# LEDMatrix.net
KiCad netlist of a schematic drawn in EAGLE
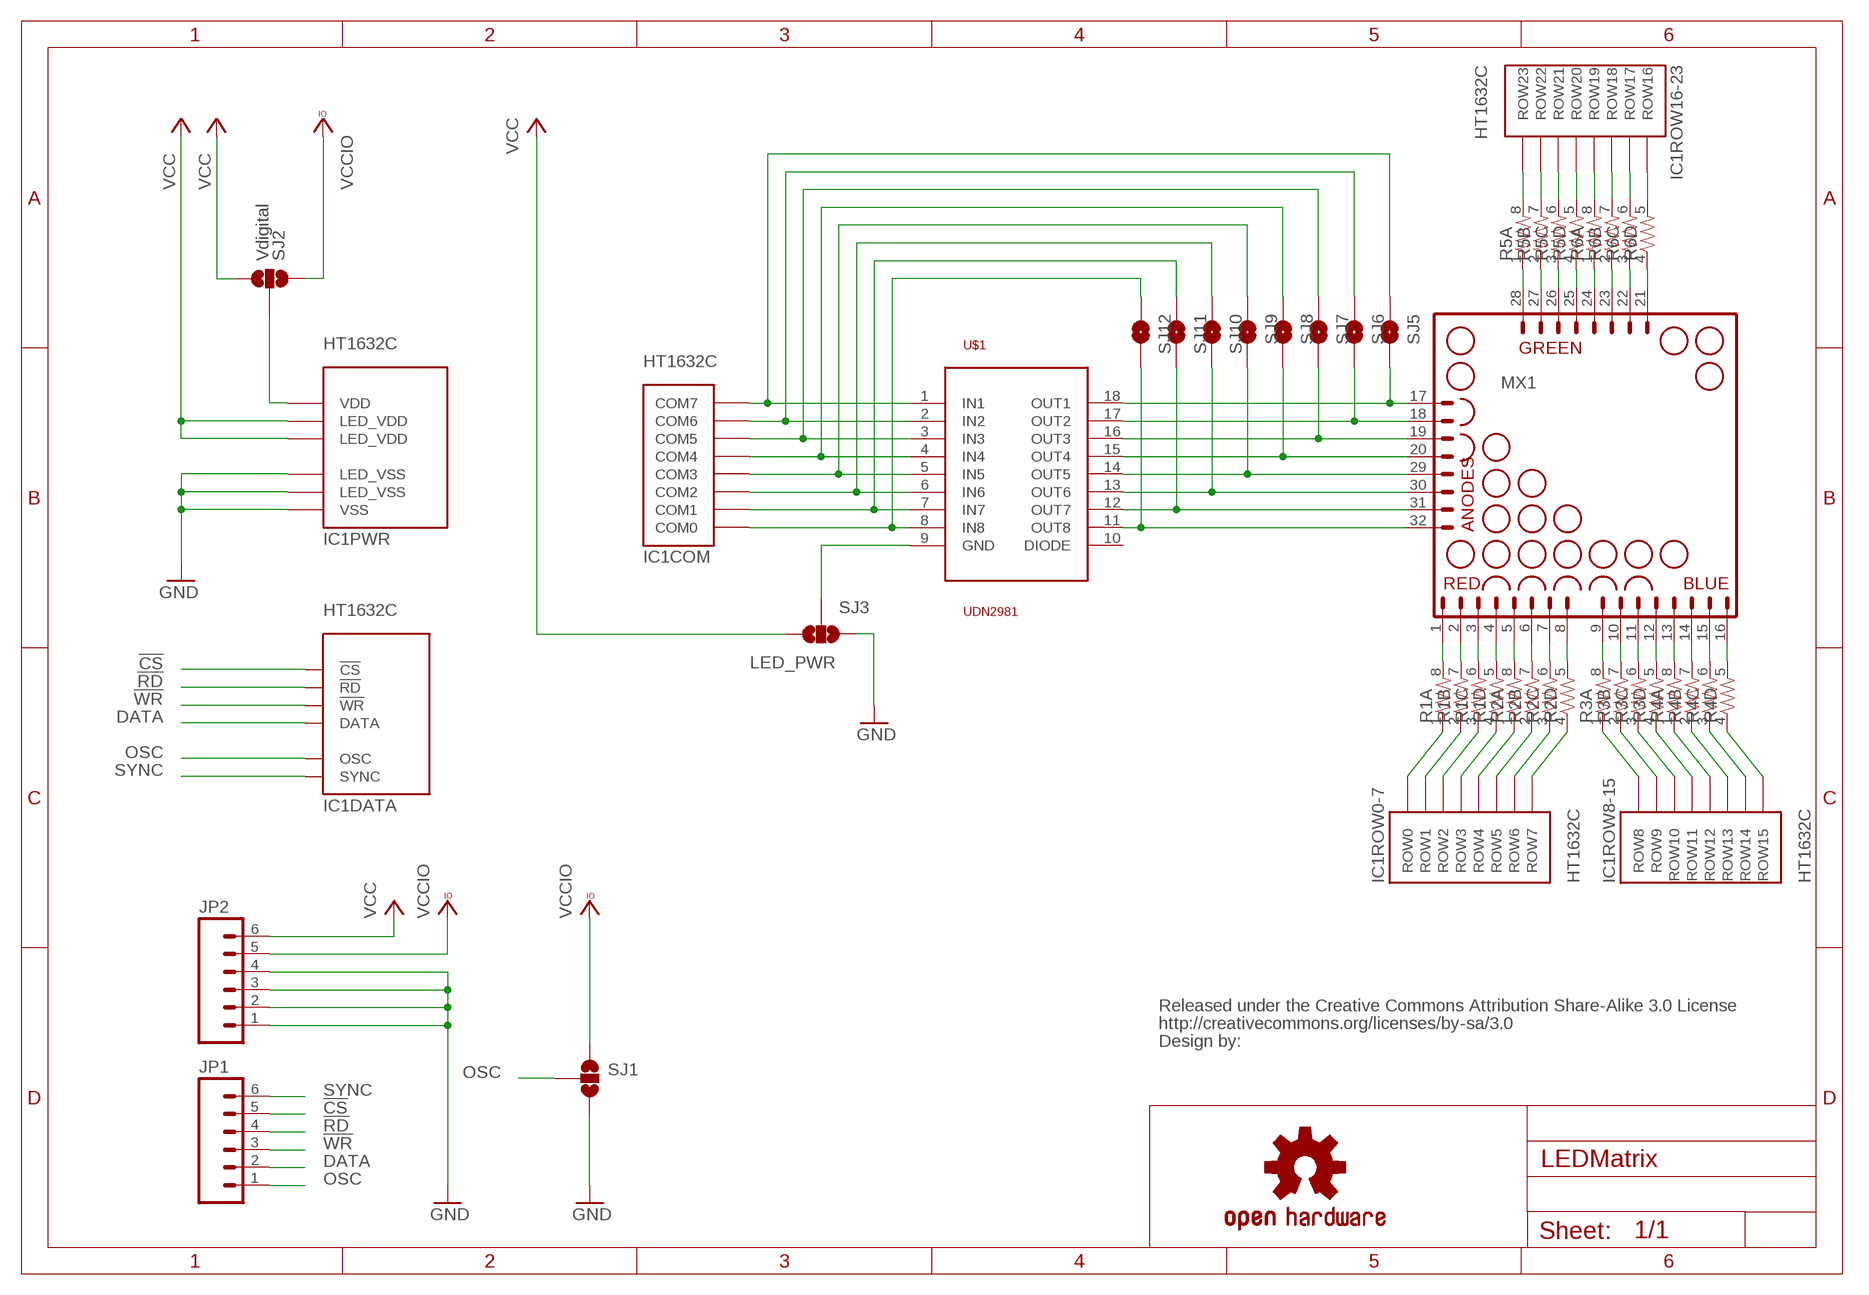
[diagram p0: schematic, sheet 1]

(export (version "E")
  (design (tool "Eeschema 10.0.6"))
  (components
    (comp (ref "CC_TEXT1")
      (value "CREATIVE_COMMONS")
      (footprint "eagle-import:CREATIVE_COMMONS")
      (libsource (lib "eagle-import") (part "CREATIVE_COMMONS"))
    )
    (comp (ref "IC1")
      (value "HT1632C")
      (footprint "eagle-import:QFP52")
      (libsource (lib "eagle-import") (part "HT1632"))
    )
    (comp (ref "JP1")
      (value "M06SIP")
      (footprint "eagle-import:1X06")
      (libsource (lib "eagle-import") (part "M06SIP"))
    )
    (comp (ref "JP2")
      (value "M06SIP")
      (footprint "eagle-import:1X06")
      (libsource (lib "eagle-import") (part "M06SIP"))
    )
    (comp (ref "LOGO1")
      (value "OSHW-LOGOL")
      (footprint "eagle-import:OSHW-LOGO-L")
      (libsource (lib "eagle-import") (part "OSHW-LOGOL"))
    )
    (comp (ref "MX1")
      (value "MATRIX_8X8_TRICOLOR_ANODE_ROW")
      (footprint "eagle-import:MATRIX_60MM_32PIN")
      (libsource (lib "eagle-import") (part "MATRIX_8X8_TRICOLOR_ANODE_ROW"))
    )
    (comp (ref "R1")
      (value "RESISTOR-ARRAY0603-ARV")
      (footprint "eagle-import:0603-ARV")
      (libsource (lib "eagle-import") (part "RESISTOR-ARRAY0603-ARV"))
    )
    (comp (ref "R2")
      (value "RESISTOR-ARRAY0603-ARV")
      (footprint "eagle-import:0603-ARV")
      (libsource (lib "eagle-import") (part "RESISTOR-ARRAY0603-ARV"))
    )
    (comp (ref "R3")
      (value "RESISTOR-ARRAY0603-ARV")
      (footprint "eagle-import:0603-ARV")
      (libsource (lib "eagle-import") (part "RESISTOR-ARRAY0603-ARV"))
    )
    (comp (ref "R4")
      (value "RESISTOR-ARRAY0603-ARV")
      (footprint "eagle-import:0603-ARV")
      (libsource (lib "eagle-import") (part "RESISTOR-ARRAY0603-ARV"))
    )
    (comp (ref "R5")
      (value "RESISTOR-ARRAY0603-ARV")
      (footprint "eagle-import:0603-ARV")
      (libsource (lib "eagle-import") (part "RESISTOR-ARRAY0603-ARV"))
    )
    (comp (ref "R6")
      (value "RESISTOR-ARRAY0603-ARV")
      (footprint "eagle-import:0603-ARV")
      (libsource (lib "eagle-import") (part "RESISTOR-ARRAY0603-ARV"))
    )
    (comp (ref "SJ1")
      (value "SOLDERJUMPER_2WAY-OLDS")
      (footprint "eagle-import:SJ_3")
      (libsource (lib "eagle-import") (part "SOLDERJUMPER_2WAY-OLDS"))
    )
    (comp (ref "SJ2")
      (value "Vdigital")
      (footprint "eagle-import:SJ_3")
      (libsource (lib "eagle-import") (part "SOLDERJUMPER_2WAY-OLDS"))
    )
    (comp (ref "SJ3")
      (value "LED_PWR")
      (footprint "eagle-import:SJ_3")
      (libsource (lib "eagle-import") (part "SOLDERJUMPER_2WAY-OLDS"))
    )
    (comp (ref "SJ5")
      (value "SOLDERJUMPER-OLDNO")
      (footprint "eagle-import:SJ_2S-NO")
      (libsource (lib "eagle-import") (part "SOLDERJUMPER-OLDNO"))
    )
    (comp (ref "SJ6")
      (value "SOLDERJUMPER-OLDNO")
      (footprint "eagle-import:SJ_2S-NO")
      (libsource (lib "eagle-import") (part "SOLDERJUMPER-OLDNO"))
    )
    (comp (ref "SJ7")
      (value "SOLDERJUMPER-OLDNO")
      (footprint "eagle-import:SJ_2S-NO")
      (libsource (lib "eagle-import") (part "SOLDERJUMPER-OLDNO"))
    )
    (comp (ref "SJ8")
      (value "SOLDERJUMPER-OLDNO")
      (footprint "eagle-import:SJ_2S-NO")
      (libsource (lib "eagle-import") (part "SOLDERJUMPER-OLDNO"))
    )
    (comp (ref "SJ9")
      (value "SOLDERJUMPER-OLDNO")
      (footprint "eagle-import:SJ_2S-NO")
      (libsource (lib "eagle-import") (part "SOLDERJUMPER-OLDNO"))
    )
    (comp (ref "SJ10")
      (value "SOLDERJUMPER-OLDNO")
      (footprint "eagle-import:SJ_2S-NO")
      (libsource (lib "eagle-import") (part "SOLDERJUMPER-OLDNO"))
    )
    (comp (ref "SJ11")
      (value "SOLDERJUMPER-OLDNO")
      (footprint "eagle-import:SJ_2S-NO")
      (libsource (lib "eagle-import") (part "SOLDERJUMPER-OLDNO"))
    )
    (comp (ref "SJ12")
      (value "SOLDERJUMPER-OLDNO")
      (footprint "eagle-import:SJ_2S-NO")
      (libsource (lib "eagle-import") (part "SOLDERJUMPER-OLDNO"))
    )
    (comp (ref "U$1")
      (value "UDN2981")
      (footprint "eagle-import:SO18L")
      (libsource (lib "eagle-import") (part "ULN2803"))
    )
  )
  (nets
    (net (code "1") (name "/DATA") (class "Default")
      (node (ref "IC1") (pin "P$16") (pinfunction "DATA_P$16") (pintype "bidirectional"))
      (node (ref "JP1") (pin "2") (pinfunction "2_2") (pintype "passive"))
    )
    (net (code "2") (name "/DIODE") (class "Default")
      (node (ref "U$1") (pin "10") (pinfunction "DIODE_10") (pintype "power_in"))
    )
    (net (code "3") (name "/OSC") (class "Default")
      (node (ref "IC1") (pin "P$15") (pinfunction "OSC_P$15") (pintype "bidirectional"))
      (node (ref "JP1") (pin "1") (pinfunction "1_1") (pintype "passive"))
      (node (ref "SJ1") (pin "2") (pinfunction "2_2") (pintype "passive"))
    )
    (net (code "4") (name "/SYNC") (class "Default")
      (node (ref "IC1") (pin "P$20") (pinfunction "SYNC_P$20") (pintype "bidirectional"))
      (node (ref "JP1") (pin "6") (pinfunction "6_6") (pintype "passive"))
    )
    (net (code "5") (name "/~{CS}") (class "Default")
      (node (ref "IC1") (pin "P$19") (pinfunction "~{CS}_P$19") (pintype "bidirectional"))
      (node (ref "JP1") (pin "5") (pinfunction "5_5") (pintype "passive"))
    )
    (net (code "6") (name "/~{RD}") (class "Default")
      (node (ref "IC1") (pin "P$18") (pinfunction "~{RD}_P$18") (pintype "bidirectional"))
      (node (ref "JP1") (pin "4") (pinfunction "4_4") (pintype "passive"))
    )
    (net (code "7") (name "/~{WR}") (class "Default")
      (node (ref "IC1") (pin "P$17") (pinfunction "~{WR}_P$17") (pintype "bidirectional"))
      (node (ref "JP1") (pin "3") (pinfunction "3_3") (pintype "passive"))
    )
    (net (code "8") (name "GND") (class "Default")
      (node (ref "IC1") (pin "P$14") (pinfunction "VSS_P$14") (pintype "bidirectional"))
      (node (ref "IC1") (pin "P$25") (pinfunction "LED_VSS_P$25") (pintype "bidirectional"))
      (node (ref "IC1") (pin "P$36") (pinfunction "LED_VSS_P$36") (pintype "bidirectional"))
      (node (ref "JP2") (pin "1") (pinfunction "1_1") (pintype "passive"))
      (node (ref "JP2") (pin "2") (pinfunction "2_2") (pintype "passive"))
      (node (ref "JP2") (pin "3") (pinfunction "3_3") (pintype "passive"))
      (node (ref "JP2") (pin "4") (pinfunction "4_4") (pintype "passive"))
      (node (ref "SJ1") (pin "3") (pinfunction "3_3") (pintype "passive"))
      (node (ref "SJ3") (pin "1") (pinfunction "1_1") (pintype "passive"))
    )
    (net (code "9") (name "Net-(IC1A-COM0)") (class "Default")
      (node (ref "IC1") (pin "P$22") (pinfunction "COM0_P$22") (pintype "bidirectional"))
      (node (ref "SJ12") (pin "1") (pinfunction "1_1") (pintype "passive"))
      (node (ref "U$1") (pin "8") (pinfunction "IN8_8") (pintype "input"))
    )
    (net (code "10") (name "Net-(IC1A-COM1)") (class "Default")
      (node (ref "IC1") (pin "P$23") (pinfunction "COM1_P$23") (pintype "bidirectional"))
      (node (ref "SJ11") (pin "1") (pinfunction "1_1") (pintype "passive"))
      (node (ref "U$1") (pin "7") (pinfunction "IN7_7") (pintype "input"))
    )
    (net (code "11") (name "Net-(IC1A-COM2)") (class "Default")
      (node (ref "IC1") (pin "P$24") (pinfunction "COM2_P$24") (pintype "bidirectional"))
      (node (ref "SJ10") (pin "1") (pinfunction "1_1") (pintype "passive"))
      (node (ref "U$1") (pin "6") (pinfunction "IN6_6") (pintype "input"))
    )
    (net (code "12") (name "Net-(IC1A-COM3)") (class "Default")
      (node (ref "IC1") (pin "P$26") (pinfunction "COM3_P$26") (pintype "bidirectional"))
      (node (ref "SJ9") (pin "1") (pinfunction "1_1") (pintype "passive"))
      (node (ref "U$1") (pin "5") (pinfunction "IN5_5") (pintype "input"))
    )
    (net (code "13") (name "Net-(IC1A-COM4)") (class "Default")
      (node (ref "IC1") (pin "P$27") (pinfunction "COM4_P$27") (pintype "bidirectional"))
      (node (ref "SJ8") (pin "1") (pinfunction "1_1") (pintype "passive"))
      (node (ref "U$1") (pin "4") (pinfunction "IN4_4") (pintype "input"))
    )
    (net (code "14") (name "Net-(IC1A-COM5)") (class "Default")
      (node (ref "IC1") (pin "P$28") (pinfunction "COM5_P$28") (pintype "bidirectional"))
      (node (ref "SJ7") (pin "1") (pinfunction "1_1") (pintype "passive"))
      (node (ref "U$1") (pin "3") (pinfunction "IN3_3") (pintype "input"))
    )
    (net (code "15") (name "Net-(IC1A-COM6)") (class "Default")
      (node (ref "IC1") (pin "P$29") (pinfunction "COM6_P$29") (pintype "bidirectional"))
      (node (ref "SJ6") (pin "1") (pinfunction "1_1") (pintype "passive"))
      (node (ref "U$1") (pin "2") (pinfunction "IN2_2") (pintype "input"))
    )
    (net (code "16") (name "Net-(IC1A-COM7)") (class "Default")
      (node (ref "IC1") (pin "P$30") (pinfunction "COM7_P$30") (pintype "bidirectional"))
      (node (ref "SJ5") (pin "1") (pinfunction "1_1") (pintype "passive"))
      (node (ref "U$1") (pin "1") (pinfunction "IN1_1") (pintype "input"))
    )
    (net (code "17") (name "Net-(IC1C-VDD)") (class "Default")
      (node (ref "IC1") (pin "P$21") (pinfunction "VDD_P$21") (pintype "bidirectional"))
      (node (ref "SJ2") (pin "2") (pinfunction "2_2") (pintype "passive"))
    )
    (net (code "18") (name "Net-(IC1D-ROW0)") (class "Default")
      (node (ref "IC1") (pin "P$13") (pinfunction "ROW0_P$13") (pintype "bidirectional"))
      (node (ref "R1") (pin "1") (pinfunction "1_1") (pintype "passive"))
    )
    (net (code "19") (name "Net-(IC1D-ROW1)") (class "Default")
      (node (ref "IC1") (pin "P$12") (pinfunction "ROW1_P$12") (pintype "bidirectional"))
      (node (ref "R1") (pin "2") (pinfunction "1_2") (pintype "passive"))
    )
    (net (code "20") (name "Net-(IC1D-ROW2)") (class "Default")
      (node (ref "IC1") (pin "P$11") (pinfunction "ROW2_P$11") (pintype "bidirectional"))
      (node (ref "R1") (pin "3") (pinfunction "1_3") (pintype "passive"))
    )
    (net (code "21") (name "Net-(IC1D-ROW3)") (class "Default")
      (node (ref "IC1") (pin "P$10") (pinfunction "ROW3_P$10") (pintype "bidirectional"))
      (node (ref "R1") (pin "4") (pinfunction "1_4") (pintype "passive"))
    )
    (net (code "22") (name "Net-(IC1D-ROW4)") (class "Default")
      (node (ref "IC1") (pin "P$9") (pinfunction "ROW4_P$9") (pintype "bidirectional"))
      (node (ref "R2") (pin "1") (pinfunction "1_1") (pintype "passive"))
    )
    (net (code "23") (name "Net-(IC1D-ROW5)") (class "Default")
      (node (ref "IC1") (pin "P$8") (pinfunction "ROW5_P$8") (pintype "bidirectional"))
      (node (ref "R2") (pin "2") (pinfunction "1_2") (pintype "passive"))
    )
    (net (code "24") (name "Net-(IC1D-ROW6)") (class "Default")
      (node (ref "IC1") (pin "P$6") (pinfunction "ROW6_P$6") (pintype "bidirectional"))
      (node (ref "R2") (pin "3") (pinfunction "1_3") (pintype "passive"))
    )
    (net (code "25") (name "Net-(IC1D-ROW7)") (class "Default")
      (node (ref "IC1") (pin "P$5") (pinfunction "ROW7_P$5") (pintype "bidirectional"))
      (node (ref "R2") (pin "4") (pinfunction "1_4") (pintype "passive"))
    )
    (net (code "26") (name "Net-(IC1E-ROW16)") (class "Default")
      (node (ref "IC1") (pin "P$48") (pinfunction "ROW16_P$48") (pintype "bidirectional"))
      (node (ref "R6") (pin "5") (pinfunction "2_5") (pintype "passive"))
    )
    (net (code "27") (name "Net-(IC1E-ROW17)") (class "Default")
      (node (ref "IC1") (pin "P$47") (pinfunction "ROW17_P$47") (pintype "bidirectional"))
      (node (ref "R6") (pin "6") (pinfunction "2_6") (pintype "passive"))
    )
    (net (code "28") (name "Net-(IC1E-ROW18)") (class "Default")
      (node (ref "IC1") (pin "P$46") (pinfunction "ROW18_P$46") (pintype "bidirectional"))
      (node (ref "R6") (pin "7") (pinfunction "2_7") (pintype "passive"))
    )
    (net (code "29") (name "Net-(IC1E-ROW19)") (class "Default")
      (node (ref "IC1") (pin "P$45") (pinfunction "ROW19_P$45") (pintype "bidirectional"))
      (node (ref "R6") (pin "8") (pinfunction "2_8") (pintype "passive"))
    )
    (net (code "30") (name "Net-(IC1E-ROW20)") (class "Default")
      (node (ref "IC1") (pin "P$44") (pinfunction "ROW20_P$44") (pintype "bidirectional"))
      (node (ref "R5") (pin "5") (pinfunction "2_5") (pintype "passive"))
    )
    (net (code "31") (name "Net-(IC1E-ROW21)") (class "Default")
      (node (ref "IC1") (pin "P$43") (pinfunction "ROW21_P$43") (pintype "bidirectional"))
      (node (ref "R5") (pin "6") (pinfunction "2_6") (pintype "passive"))
    )
    (net (code "32") (name "Net-(IC1E-ROW22)") (class "Default")
      (node (ref "IC1") (pin "P$42") (pinfunction "ROW22_P$42") (pintype "bidirectional"))
      (node (ref "R5") (pin "7") (pinfunction "2_7") (pintype "passive"))
    )
    (net (code "33") (name "Net-(IC1E-ROW23)") (class "Default")
      (node (ref "IC1") (pin "P$41") (pinfunction "ROW23_P$41") (pintype "bidirectional"))
      (node (ref "R5") (pin "8") (pinfunction "2_8") (pintype "passive"))
    )
    (net (code "34") (name "Net-(IC1G-ROW8)") (class "Default")
      (node (ref "IC1") (pin "P$4") (pinfunction "ROW8_P$4") (pintype "bidirectional"))
      (node (ref "R3") (pin "1") (pinfunction "1_1") (pintype "passive"))
    )
    (net (code "35") (name "Net-(IC1G-ROW9)") (class "Default")
      (node (ref "IC1") (pin "P$3") (pinfunction "ROW9_P$3") (pintype "bidirectional"))
      (node (ref "R3") (pin "2") (pinfunction "1_2") (pintype "passive"))
    )
    (net (code "36") (name "Net-(IC1G-ROW10)") (class "Default")
      (node (ref "IC1") (pin "P$2") (pinfunction "ROW10_P$2") (pintype "bidirectional"))
      (node (ref "R3") (pin "3") (pinfunction "1_3") (pintype "passive"))
    )
    (net (code "37") (name "Net-(IC1G-ROW11)") (class "Default")
      (node (ref "IC1") (pin "P$1") (pinfunction "ROW11_P$1") (pintype "bidirectional"))
      (node (ref "R3") (pin "4") (pinfunction "1_4") (pintype "passive"))
    )
    (net (code "38") (name "Net-(IC1G-ROW12)") (class "Default")
      (node (ref "IC1") (pin "P$52") (pinfunction "ROW12_P$52") (pintype "bidirectional"))
      (node (ref "R4") (pin "1") (pinfunction "1_1") (pintype "passive"))
    )
    (net (code "39") (name "Net-(IC1G-ROW13)") (class "Default")
      (node (ref "IC1") (pin "P$51") (pinfunction "ROW13_P$51") (pintype "bidirectional"))
      (node (ref "R4") (pin "2") (pinfunction "1_2") (pintype "passive"))
    )
    (net (code "40") (name "Net-(IC1G-ROW14)") (class "Default")
      (node (ref "IC1") (pin "P$50") (pinfunction "ROW14_P$50") (pintype "bidirectional"))
      (node (ref "R4") (pin "3") (pinfunction "1_3") (pintype "passive"))
    )
    (net (code "41") (name "Net-(IC1G-ROW15)") (class "Default")
      (node (ref "IC1") (pin "P$49") (pinfunction "ROW15_P$49") (pintype "bidirectional"))
      (node (ref "R4") (pin "4") (pinfunction "1_4") (pintype "passive"))
    )
    (net (code "42") (name "Net-(MX1-Pad24)") (class "Default")
      (node (ref "MX1") (pin "24") (pinfunction "24_24") (pintype "passive"))
      (node (ref "R6") (pin "1") (pinfunction "1_1") (pintype "passive"))
    )
    (net (code "43") (name "Net-(MX1-Pad28)") (class "Default")
      (node (ref "MX1") (pin "28") (pinfunction "28_28") (pintype "passive"))
      (node (ref "R5") (pin "1") (pinfunction "1_1") (pintype "passive"))
    )
    (net (code "44") (name "Net-(R1A-2)") (class "Default")
      (node (ref "MX1") (pin "1") (pinfunction "1_1") (pintype "passive"))
      (node (ref "R1") (pin "8") (pinfunction "2_8") (pintype "passive"))
    )
    (net (code "45") (name "Net-(R1B-2)") (class "Default")
      (node (ref "MX1") (pin "2") (pinfunction "2_2") (pintype "passive"))
      (node (ref "R1") (pin "7") (pinfunction "2_7") (pintype "passive"))
    )
    (net (code "46") (name "Net-(R1C-2)") (class "Default")
      (node (ref "MX1") (pin "3") (pinfunction "3_3") (pintype "passive"))
      (node (ref "R1") (pin "6") (pinfunction "2_6") (pintype "passive"))
    )
    (net (code "47") (name "Net-(R1D-2)") (class "Default")
      (node (ref "MX1") (pin "4") (pinfunction "4_4") (pintype "passive"))
      (node (ref "R1") (pin "5") (pinfunction "2_5") (pintype "passive"))
    )
    (net (code "48") (name "Net-(R2A-2)") (class "Default")
      (node (ref "MX1") (pin "5") (pinfunction "5_5") (pintype "passive"))
      (node (ref "R2") (pin "8") (pinfunction "2_8") (pintype "passive"))
    )
    (net (code "49") (name "Net-(R2B-2)") (class "Default")
      (node (ref "MX1") (pin "6") (pinfunction "6_6") (pintype "passive"))
      (node (ref "R2") (pin "7") (pinfunction "2_7") (pintype "passive"))
    )
    (net (code "50") (name "Net-(R2C-2)") (class "Default")
      (node (ref "MX1") (pin "7") (pinfunction "7_7") (pintype "passive"))
      (node (ref "R2") (pin "6") (pinfunction "2_6") (pintype "passive"))
    )
    (net (code "51") (name "Net-(R2D-2)") (class "Default")
      (node (ref "MX1") (pin "8") (pinfunction "8_8") (pintype "passive"))
      (node (ref "R2") (pin "5") (pinfunction "2_5") (pintype "passive"))
    )
    (net (code "52") (name "Net-(R3A-2)") (class "Default")
      (node (ref "MX1") (pin "9") (pinfunction "9_9") (pintype "passive"))
      (node (ref "R3") (pin "8") (pinfunction "2_8") (pintype "passive"))
    )
    (net (code "53") (name "Net-(R3B-2)") (class "Default")
      (node (ref "MX1") (pin "10") (pinfunction "10_10") (pintype "passive"))
      (node (ref "R3") (pin "7") (pinfunction "2_7") (pintype "passive"))
    )
    (net (code "54") (name "Net-(R3C-2)") (class "Default")
      (node (ref "MX1") (pin "11") (pinfunction "11_11") (pintype "passive"))
      (node (ref "R3") (pin "6") (pinfunction "2_6") (pintype "passive"))
    )
    (net (code "55") (name "Net-(R3D-2)") (class "Default")
      (node (ref "MX1") (pin "12") (pinfunction "12_12") (pintype "passive"))
      (node (ref "R3") (pin "5") (pinfunction "2_5") (pintype "passive"))
    )
    (net (code "56") (name "Net-(R4A-2)") (class "Default")
      (node (ref "MX1") (pin "13") (pinfunction "13_13") (pintype "passive"))
      (node (ref "R4") (pin "8") (pinfunction "2_8") (pintype "passive"))
    )
    (net (code "57") (name "Net-(R4B-2)") (class "Default")
      (node (ref "MX1") (pin "14") (pinfunction "14_14") (pintype "passive"))
      (node (ref "R4") (pin "7") (pinfunction "2_7") (pintype "passive"))
    )
    (net (code "58") (name "Net-(R4C-2)") (class "Default")
      (node (ref "MX1") (pin "15") (pinfunction "15_15") (pintype "passive"))
      (node (ref "R4") (pin "6") (pinfunction "2_6") (pintype "passive"))
    )
    (net (code "59") (name "Net-(R4D-2)") (class "Default")
      (node (ref "MX1") (pin "16") (pinfunction "16_16") (pintype "passive"))
      (node (ref "R4") (pin "5") (pinfunction "2_5") (pintype "passive"))
    )
    (net (code "60") (name "Net-(R5B-1)") (class "Default")
      (node (ref "MX1") (pin "27") (pinfunction "27_27") (pintype "passive"))
      (node (ref "R5") (pin "2") (pinfunction "1_2") (pintype "passive"))
    )
    (net (code "61") (name "Net-(R5C-1)") (class "Default")
      (node (ref "MX1") (pin "26") (pinfunction "26_26") (pintype "passive"))
      (node (ref "R5") (pin "3") (pinfunction "1_3") (pintype "passive"))
    )
    (net (code "62") (name "Net-(R5D-1)") (class "Default")
      (node (ref "MX1") (pin "25") (pinfunction "25_25") (pintype "passive"))
      (node (ref "R5") (pin "4") (pinfunction "1_4") (pintype "passive"))
    )
    (net (code "63") (name "Net-(R6B-1)") (class "Default")
      (node (ref "MX1") (pin "23") (pinfunction "23_23") (pintype "passive"))
      (node (ref "R6") (pin "2") (pinfunction "1_2") (pintype "passive"))
    )
    (net (code "64") (name "Net-(R6C-1)") (class "Default")
      (node (ref "MX1") (pin "22") (pinfunction "22_22") (pintype "passive"))
      (node (ref "R6") (pin "3") (pinfunction "1_3") (pintype "passive"))
    )
    (net (code "65") (name "Net-(R6D-1)") (class "Default")
      (node (ref "MX1") (pin "21") (pinfunction "21_21") (pintype "passive"))
      (node (ref "R6") (pin "4") (pinfunction "1_4") (pintype "passive"))
    )
    (net (code "66") (name "Net-(U$1-GND)") (class "Default")
      (node (ref "SJ3") (pin "2") (pinfunction "2_2") (pintype "passive"))
      (node (ref "U$1") (pin "9") (pinfunction "GND_9") (pintype "power_in"))
    )
    (net (code "67") (name "Net-(U$1-OUT1)") (class "Default")
      (node (ref "MX1") (pin "17") (pinfunction "17_17") (pintype "passive"))
      (node (ref "SJ5") (pin "2") (pinfunction "2_2") (pintype "passive"))
      (node (ref "U$1") (pin "18") (pinfunction "OUT1_18") (pintype "open_collector"))
    )
    (net (code "68") (name "Net-(U$1-OUT2)") (class "Default")
      (node (ref "MX1") (pin "18") (pinfunction "18_18") (pintype "passive"))
      (node (ref "SJ6") (pin "2") (pinfunction "2_2") (pintype "passive"))
      (node (ref "U$1") (pin "17") (pinfunction "OUT2_17") (pintype "open_collector"))
    )
    (net (code "69") (name "Net-(U$1-OUT3)") (class "Default")
      (node (ref "MX1") (pin "19") (pinfunction "19_19") (pintype "passive"))
      (node (ref "SJ7") (pin "2") (pinfunction "2_2") (pintype "passive"))
      (node (ref "U$1") (pin "16") (pinfunction "OUT3_16") (pintype "open_collector"))
    )
    (net (code "70") (name "Net-(U$1-OUT4)") (class "Default")
      (node (ref "MX1") (pin "20") (pinfunction "20_20") (pintype "passive"))
      (node (ref "SJ8") (pin "2") (pinfunction "2_2") (pintype "passive"))
      (node (ref "U$1") (pin "15") (pinfunction "OUT4_15") (pintype "open_collector"))
    )
    (net (code "71") (name "Net-(U$1-OUT5)") (class "Default")
      (node (ref "MX1") (pin "29") (pinfunction "29_29") (pintype "passive"))
      (node (ref "SJ9") (pin "2") (pinfunction "2_2") (pintype "passive"))
      (node (ref "U$1") (pin "14") (pinfunction "OUT5_14") (pintype "open_collector"))
    )
    (net (code "72") (name "Net-(U$1-OUT6)") (class "Default")
      (node (ref "MX1") (pin "30") (pinfunction "30_30") (pintype "passive"))
      (node (ref "SJ10") (pin "2") (pinfunction "2_2") (pintype "passive"))
      (node (ref "U$1") (pin "13") (pinfunction "OUT6_13") (pintype "open_collector"))
    )
    (net (code "73") (name "Net-(U$1-OUT7)") (class "Default")
      (node (ref "MX1") (pin "31") (pinfunction "31_31") (pintype "passive"))
      (node (ref "SJ11") (pin "2") (pinfunction "2_2") (pintype "passive"))
      (node (ref "U$1") (pin "12") (pinfunction "OUT7_12") (pintype "open_collector"))
    )
    (net (code "74") (name "Net-(U$1-OUT8)") (class "Default")
      (node (ref "MX1") (pin "32") (pinfunction "32_32") (pintype "passive"))
      (node (ref "SJ12") (pin "2") (pinfunction "2_2") (pintype "passive"))
      (node (ref "U$1") (pin "11") (pinfunction "OUT8_11") (pintype "open_collector"))
    )
    (net (code "75") (name "VCC") (class "Default")
      (node (ref "IC1") (pin "P$38") (pinfunction "LED_VDD_P$38") (pintype "bidirectional"))
      (node (ref "IC1") (pin "P$7") (pinfunction "LED_VDD_P$7") (pintype "bidirectional"))
      (node (ref "JP2") (pin "6") (pinfunction "6_6") (pintype "passive"))
      (node (ref "SJ2") (pin "3") (pinfunction "3_3") (pintype "passive"))
      (node (ref "SJ3") (pin "3") (pinfunction "3_3") (pintype "passive"))
    )
    (net (code "76") (name "VCCIO") (class "Default")
      (node (ref "JP2") (pin "5") (pinfunction "5_5") (pintype "passive"))
      (node (ref "SJ1") (pin "1") (pinfunction "1_1") (pintype "passive"))
      (node (ref "SJ2") (pin "1") (pinfunction "1_1") (pintype "passive"))
    )
  )
)
